# Unified_Circuit.net
KiCad netlist of a schematic drawn in EAGLE
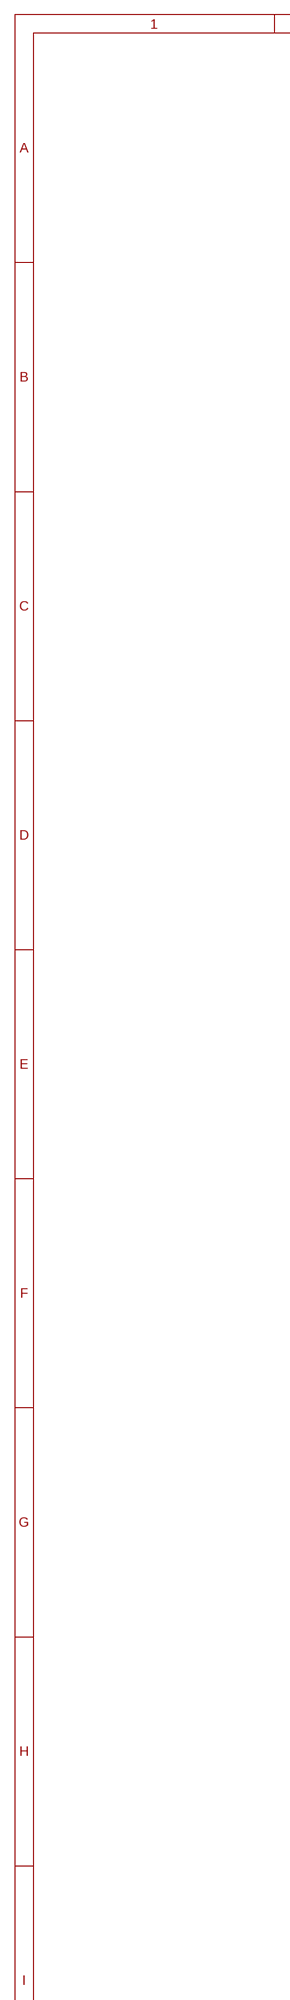
[diagram p0: schematic, sheet 1, part 1 of 2]
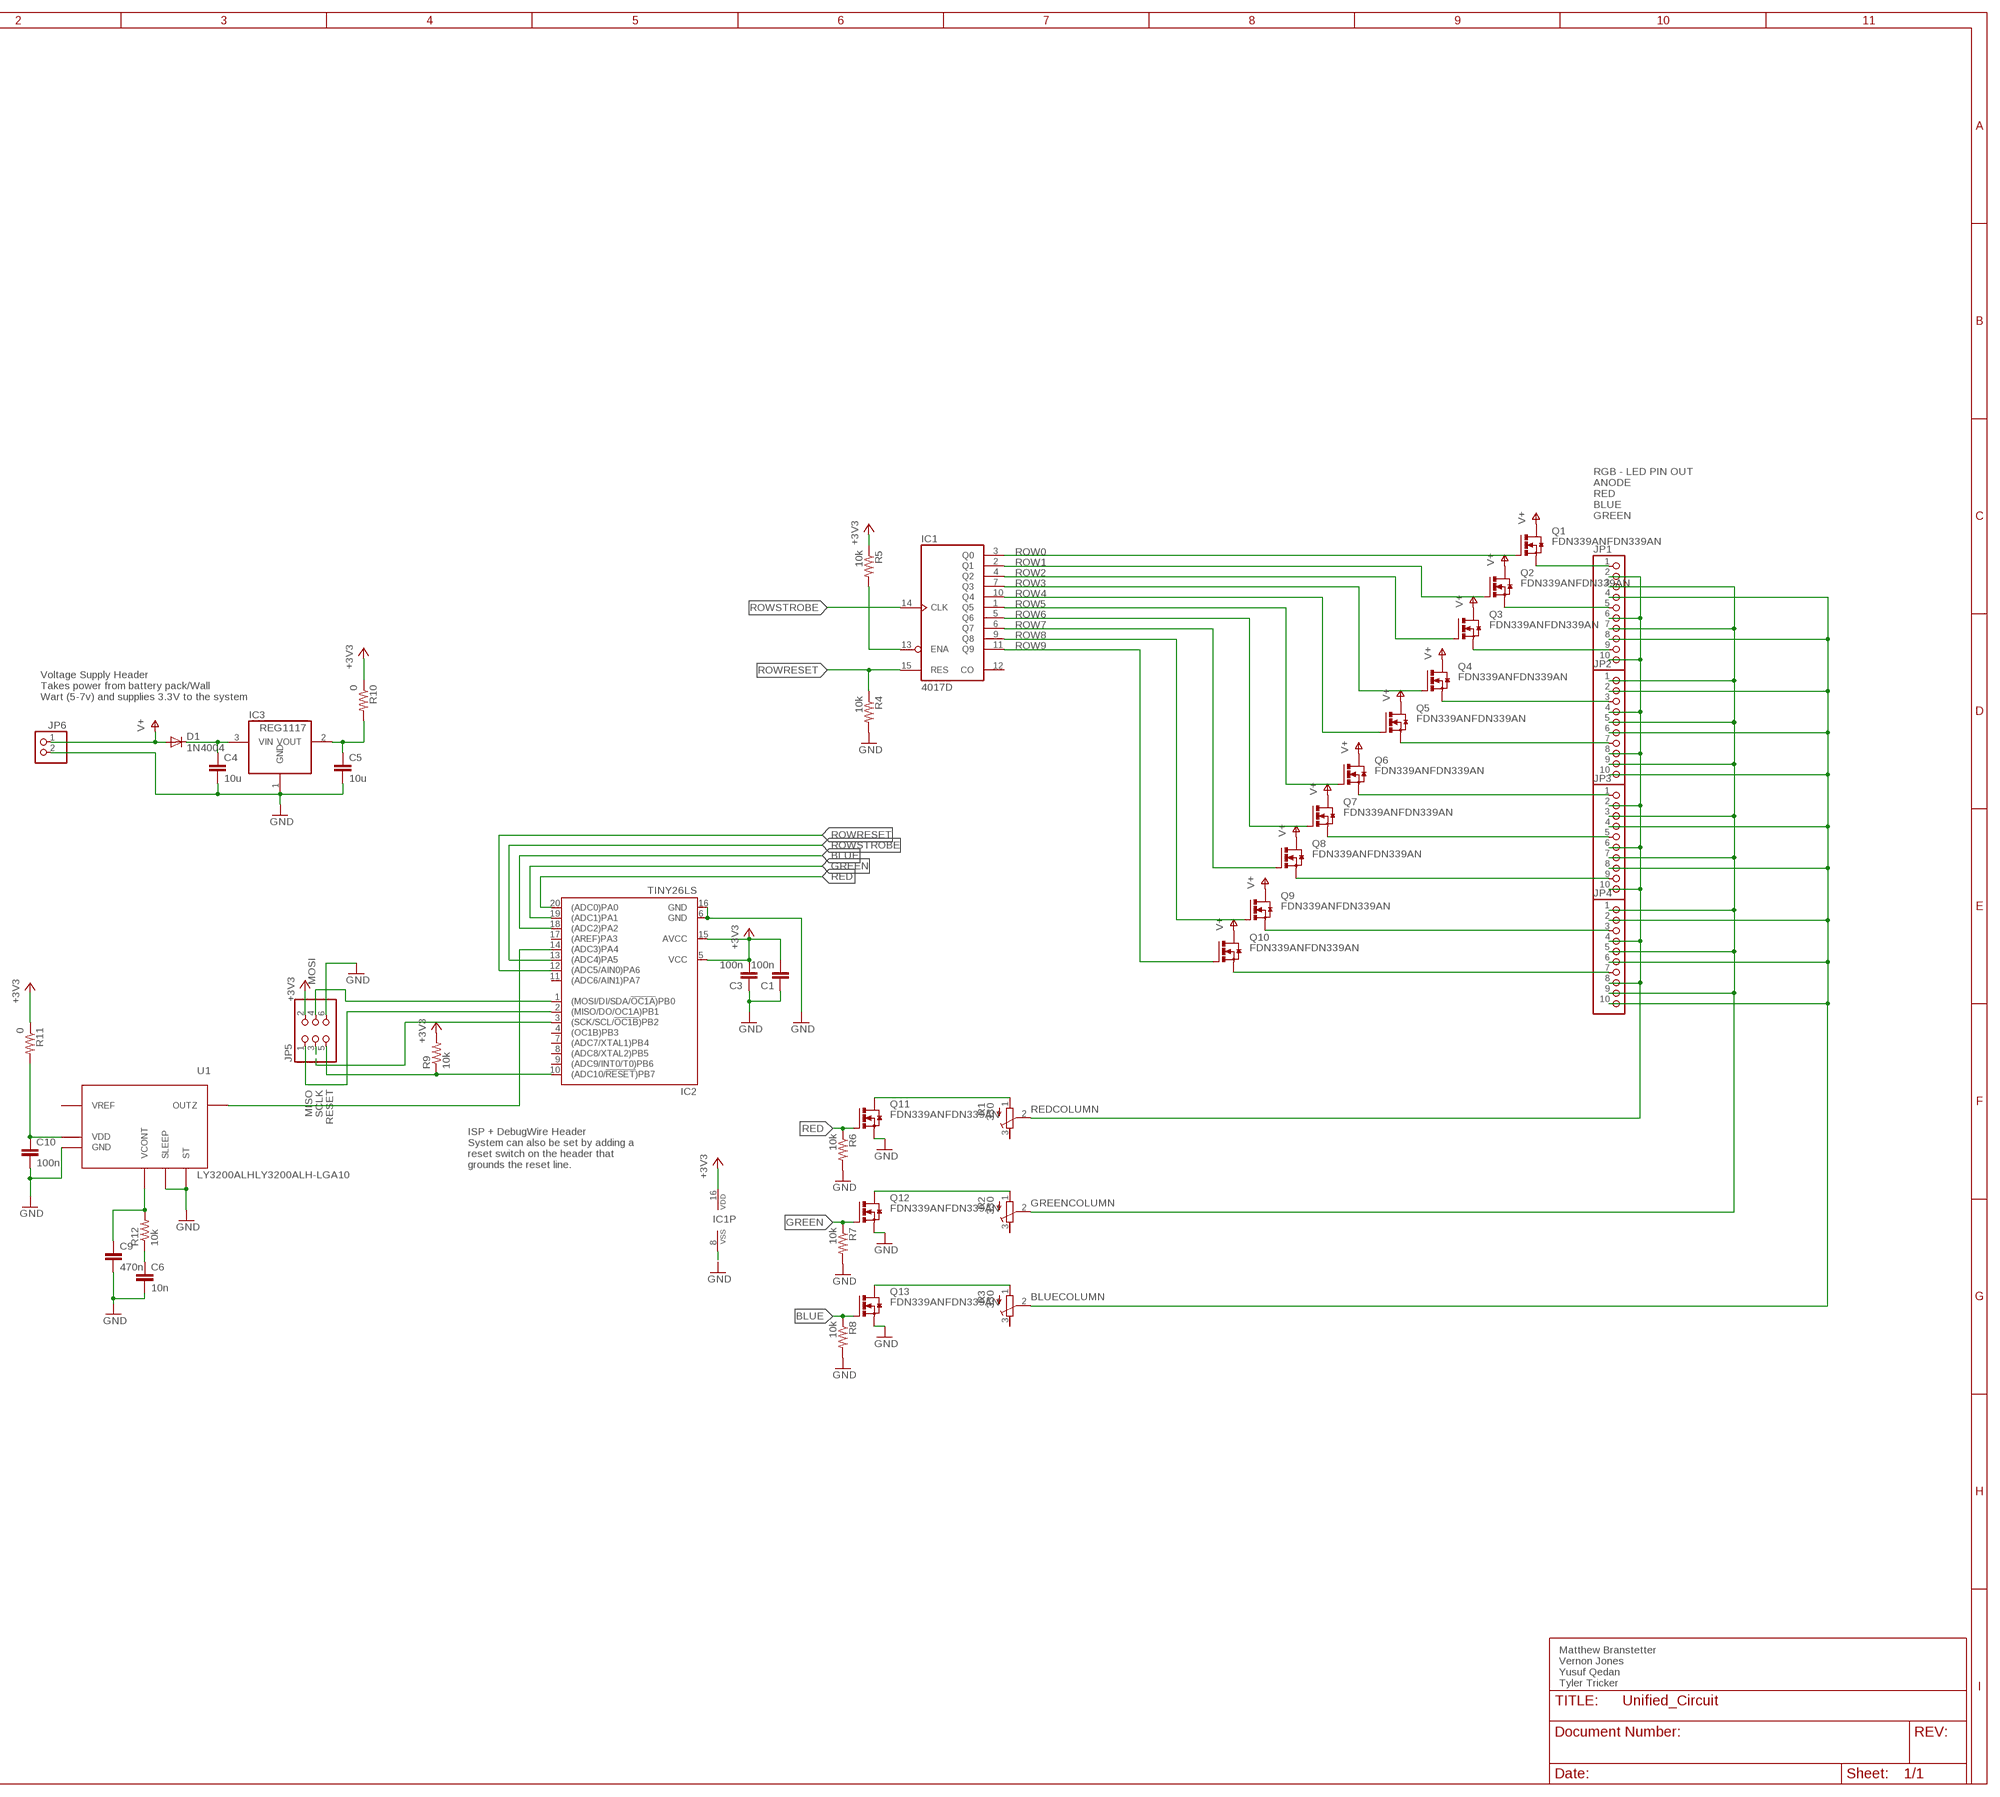
[diagram p1: schematic, sheet 1, part 2 of 2]

(export (version "E")
  (design (tool "Eeschema 10.0.6"))
  (components
    (comp (ref "C1")
      (value "100n")
      (footprint "eagle-import:C0805")
      (libsource (lib "eagle-import") (part "C-EUC0805"))
    )
    (comp (ref "C3")
      (value "100n")
      (footprint "eagle-import:C0805")
      (libsource (lib "eagle-import") (part "C-EUC0805"))
    )
    (comp (ref "C4")
      (value "10u")
      (footprint "eagle-import:C0805")
      (libsource (lib "eagle-import") (part "C-EUC0805"))
    )
    (comp (ref "C5")
      (value "10u")
      (footprint "eagle-import:C0805")
      (libsource (lib "eagle-import") (part "C-EUC0805"))
    )
    (comp (ref "C6")
      (value "10n")
      (footprint "eagle-import:C0805")
      (libsource (lib "eagle-import") (part "C-EUC0805"))
    )
    (comp (ref "C9")
      (value "470n")
      (footprint "eagle-import:C0805")
      (libsource (lib "eagle-import") (part "C-EUC0805"))
    )
    (comp (ref "C10")
      (value "100n")
      (footprint "eagle-import:C0805")
      (libsource (lib "eagle-import") (part "C-EUC0805"))
    )
    (comp (ref "D1")
      (value "1N4004")
      (footprint "eagle-import:DO41-10")
      (libsource (lib "eagle-import") (part "1N4004"))
    )
    (comp (ref "IC1")
      (value "4017D")
      (footprint "eagle-import:SO16")
      (libsource (lib "eagle-import") (part "4017D"))
    )
    (comp (ref "IC2")
      (value "TINY26LS")
      (footprint "eagle-import:SO20L")
      (fields (field (name "MPN") "ATTINY26L-8SU"))
      (libsource (lib "eagle-import") (part "TINY26SL"))
    )
    (comp (ref "IC3")
      (value "REG1117")
      (footprint "eagle-import:SOT223")
      (libsource (lib "eagle-import") (part "REG1117"))
    )
    (comp (ref "JP1")
      (value "PINHD-1X10/90")
      (footprint "eagle-import:1X10_90")
      (libsource (lib "eagle-import") (part "PINHD-1X10/90"))
    )
    (comp (ref "JP2")
      (value "PINHD-1X10/90")
      (footprint "eagle-import:1X10_90")
      (libsource (lib "eagle-import") (part "PINHD-1X10/90"))
    )
    (comp (ref "JP3")
      (value "PINHD-1X10/90")
      (footprint "eagle-import:1X10_90")
      (libsource (lib "eagle-import") (part "PINHD-1X10/90"))
    )
    (comp (ref "JP4")
      (value "PINHD-1X10/90")
      (footprint "eagle-import:1X10_90")
      (libsource (lib "eagle-import") (part "PINHD-1X10/90"))
    )
    (comp (ref "JP5")
      (value "PINHD-2X3")
      (footprint "eagle-import:2X03")
      (libsource (lib "eagle-import") (part "PINHD-2X3"))
    )
    (comp (ref "JP6")
      (value "PINHD-1X2")
      (footprint "eagle-import:1X02")
      (libsource (lib "eagle-import") (part "PINHD-1X2"))
    )
    (comp (ref "Q1")
      (value "FDN339ANFDN339AN")
      (footprint "eagle-import:SSOT-3")
      (libsource (lib "eagle-import") (part "FDN339ANFDN339AN"))
    )
    (comp (ref "Q2")
      (value "FDN339ANFDN339AN")
      (footprint "eagle-import:SSOT-3")
      (libsource (lib "eagle-import") (part "FDN339ANFDN339AN"))
    )
    (comp (ref "Q3")
      (value "FDN339ANFDN339AN")
      (footprint "eagle-import:SSOT-3")
      (libsource (lib "eagle-import") (part "FDN339ANFDN339AN"))
    )
    (comp (ref "Q4")
      (value "FDN339ANFDN339AN")
      (footprint "eagle-import:SSOT-3")
      (libsource (lib "eagle-import") (part "FDN339ANFDN339AN"))
    )
    (comp (ref "Q5")
      (value "FDN339ANFDN339AN")
      (footprint "eagle-import:SSOT-3")
      (libsource (lib "eagle-import") (part "FDN339ANFDN339AN"))
    )
    (comp (ref "Q6")
      (value "FDN339ANFDN339AN")
      (footprint "eagle-import:SSOT-3")
      (libsource (lib "eagle-import") (part "FDN339ANFDN339AN"))
    )
    (comp (ref "Q7")
      (value "FDN339ANFDN339AN")
      (footprint "eagle-import:SSOT-3")
      (libsource (lib "eagle-import") (part "FDN339ANFDN339AN"))
    )
    (comp (ref "Q8")
      (value "FDN339ANFDN339AN")
      (footprint "eagle-import:SSOT-3")
      (libsource (lib "eagle-import") (part "FDN339ANFDN339AN"))
    )
    (comp (ref "Q9")
      (value "FDN339ANFDN339AN")
      (footprint "eagle-import:SSOT-3")
      (libsource (lib "eagle-import") (part "FDN339ANFDN339AN"))
    )
    (comp (ref "Q10")
      (value "FDN339ANFDN339AN")
      (footprint "eagle-import:SSOT-3")
      (libsource (lib "eagle-import") (part "FDN339ANFDN339AN"))
    )
    (comp (ref "Q11")
      (value "FDN339ANFDN339AN")
      (footprint "eagle-import:SSOT-3")
      (libsource (lib "eagle-import") (part "FDN339ANFDN339AN"))
    )
    (comp (ref "Q12")
      (value "FDN339ANFDN339AN")
      (footprint "eagle-import:SSOT-3")
      (libsource (lib "eagle-import") (part "FDN339ANFDN339AN"))
    )
    (comp (ref "Q13")
      (value "FDN339ANFDN339AN")
      (footprint "eagle-import:SSOT-3")
      (libsource (lib "eagle-import") (part "FDN339ANFDN339AN"))
    )
    (comp (ref "R1")
      (value "330")
      (footprint "eagle-import:RTRIM3224W")
      (libsource (lib "eagle-import") (part "R-TRIMM3224W"))
    )
    (comp (ref "R2")
      (value "330")
      (footprint "eagle-import:RTRIM3224W")
      (libsource (lib "eagle-import") (part "R-TRIMM3224W"))
    )
    (comp (ref "R3")
      (value "330")
      (footprint "eagle-import:RTRIM3224W")
      (libsource (lib "eagle-import") (part "R-TRIMM3224W"))
    )
    (comp (ref "R4")
      (value "10k")
      (footprint "eagle-import:R0805")
      (libsource (lib "eagle-import") (part "R-US_R0805"))
    )
    (comp (ref "R5")
      (value "10k")
      (footprint "eagle-import:R0805")
      (libsource (lib "eagle-import") (part "R-US_R0805"))
    )
    (comp (ref "R6")
      (value "10k")
      (footprint "eagle-import:R0805")
      (libsource (lib "eagle-import") (part "R-US_R0805"))
    )
    (comp (ref "R7")
      (value "10k")
      (footprint "eagle-import:R0805")
      (libsource (lib "eagle-import") (part "R-US_R0805"))
    )
    (comp (ref "R8")
      (value "10k")
      (footprint "eagle-import:R0805")
      (libsource (lib "eagle-import") (part "R-US_R0805"))
    )
    (comp (ref "R9")
      (value "10k")
      (footprint "eagle-import:R0805")
      (libsource (lib "eagle-import") (part "R-US_R0805"))
    )
    (comp (ref "R10")
      (value "0")
      (footprint "eagle-import:R0805")
      (libsource (lib "eagle-import") (part "R-US_R0805"))
    )
    (comp (ref "R11")
      (value "0")
      (footprint "eagle-import:R0805")
      (libsource (lib "eagle-import") (part "R-US_R0805"))
    )
    (comp (ref "R12")
      (value "10k")
      (footprint "eagle-import:R0805")
      (libsource (lib "eagle-import") (part "R-US_R0805"))
    )
    (comp (ref "U1")
      (value "LY3200ALHLY3200ALH-LGA10")
      (footprint "eagle-import:LGA10")
      (libsource (lib "eagle-import") (part "LY3200ALHLY3200ALH-LGA10"))
    )
  )
  (nets
    (net (code "1") (name "+3V3") (class "Default")
      (node (ref "C1") (pin "2") (pinfunction "2_2") (pintype "passive"))
      (node (ref "C3") (pin "2") (pinfunction "2_2") (pintype "passive"))
      (node (ref "IC1") (pin "16") (pinfunction "VDD_16") (pintype "power_in"))
      (node (ref "IC2") (pin "15") (pinfunction "AVCC_15") (pintype "power_in"))
      (node (ref "IC2") (pin "5") (pinfunction "VCC_5") (pintype "power_in"))
      (node (ref "JP5") (pin "2") (pinfunction "2_2") (pintype "passive"))
      (node (ref "R10") (pin "1") (pinfunction "1_1") (pintype "passive"))
      (node (ref "R11") (pin "1") (pinfunction "1_1") (pintype "passive"))
      (node (ref "R5") (pin "1") (pinfunction "1_1") (pintype "passive"))
      (node (ref "R9") (pin "2") (pinfunction "2_2") (pintype "passive"))
    )
    (net (code "2") (name "/BLUECOLUMN") (class "Default")
      (node (ref "JP1") (pin "4") (pinfunction "4_4") (pintype "passive"))
      (node (ref "JP1") (pin "8") (pinfunction "8_8") (pintype "passive"))
      (node (ref "JP2") (pin "10") (pinfunction "10_10") (pintype "passive"))
      (node (ref "JP2") (pin "2") (pinfunction "2_2") (pintype "passive"))
      (node (ref "JP2") (pin "6") (pinfunction "6_6") (pintype "passive"))
      (node (ref "JP3") (pin "4") (pinfunction "4_4") (pintype "passive"))
      (node (ref "JP3") (pin "8") (pinfunction "8_8") (pintype "passive"))
      (node (ref "JP4") (pin "10") (pinfunction "10_10") (pintype "passive"))
      (node (ref "JP4") (pin "2") (pinfunction "2_2") (pintype "passive"))
      (node (ref "JP4") (pin "6") (pinfunction "6_6") (pintype "passive"))
      (node (ref "R3") (pin "2") (pinfunction "S_2") (pintype "passive"))
    )
    (net (code "3") (name "/GREENCOLUMN") (class "Default")
      (node (ref "JP1") (pin "3") (pinfunction "3_3") (pintype "passive"))
      (node (ref "JP1") (pin "7") (pinfunction "7_7") (pintype "passive"))
      (node (ref "JP2") (pin "1") (pinfunction "1_1") (pintype "passive"))
      (node (ref "JP2") (pin "5") (pinfunction "5_5") (pintype "passive"))
      (node (ref "JP2") (pin "9") (pinfunction "9_9") (pintype "passive"))
      (node (ref "JP3") (pin "3") (pinfunction "3_3") (pintype "passive"))
      (node (ref "JP3") (pin "7") (pinfunction "7_7") (pintype "passive"))
      (node (ref "JP4") (pin "1") (pinfunction "1_1") (pintype "passive"))
      (node (ref "JP4") (pin "5") (pinfunction "5_5") (pintype "passive"))
      (node (ref "JP4") (pin "9") (pinfunction "9_9") (pintype "passive"))
      (node (ref "R2") (pin "2") (pinfunction "S_2") (pintype "passive"))
    )
    (net (code "4") (name "/MISO") (class "Default")
      (node (ref "IC2") (pin "2") (pinfunction "(MISO/DO/OC1A)PB1_2") (pintype "bidirectional"))
      (node (ref "JP5") (pin "1") (pinfunction "1_1") (pintype "passive"))
    )
    (net (code "5") (name "/MOSI") (class "Default")
      (node (ref "IC2") (pin "1") (pinfunction "(MOSI/DI/SDA/~{OC1A})PB0_1") (pintype "bidirectional"))
      (node (ref "JP5") (pin "4") (pinfunction "4_4") (pintype "passive"))
    )
    (net (code "6") (name "/REDCOLUMN") (class "Default")
      (node (ref "JP1") (pin "10") (pinfunction "10_10") (pintype "passive"))
      (node (ref "JP1") (pin "2") (pinfunction "2_2") (pintype "passive"))
      (node (ref "JP1") (pin "6") (pinfunction "6_6") (pintype "passive"))
      (node (ref "JP2") (pin "4") (pinfunction "4_4") (pintype "passive"))
      (node (ref "JP2") (pin "8") (pinfunction "8_8") (pintype "passive"))
      (node (ref "JP3") (pin "10") (pinfunction "10_10") (pintype "passive"))
      (node (ref "JP3") (pin "2") (pinfunction "2_2") (pintype "passive"))
      (node (ref "JP3") (pin "6") (pinfunction "6_6") (pintype "passive"))
      (node (ref "JP4") (pin "4") (pinfunction "4_4") (pintype "passive"))
      (node (ref "JP4") (pin "8") (pinfunction "8_8") (pintype "passive"))
      (node (ref "R1") (pin "2") (pinfunction "S_2") (pintype "passive"))
    )
    (net (code "7") (name "/RESET") (class "Default")
      (node (ref "IC2") (pin "10") (pinfunction "(ADC10/~{RESET})PB7_10") (pintype "bidirectional"))
      (node (ref "JP5") (pin "5") (pinfunction "5_5") (pintype "passive"))
      (node (ref "R9") (pin "1") (pinfunction "1_1") (pintype "passive"))
    )
    (net (code "8") (name "/ROW0") (class "Default")
      (node (ref "IC1") (pin "3") (pinfunction "Q0_3") (pintype "output"))
      (node (ref "Q1") (pin "P$2") (pinfunction "G_P$2") (pintype "passive"))
    )
    (net (code "9") (name "/ROW1") (class "Default")
      (node (ref "IC1") (pin "2") (pinfunction "Q1_2") (pintype "output"))
      (node (ref "Q2") (pin "P$2") (pinfunction "G_P$2") (pintype "passive"))
    )
    (net (code "10") (name "/ROW2") (class "Default")
      (node (ref "IC1") (pin "4") (pinfunction "Q2_4") (pintype "output"))
      (node (ref "Q3") (pin "P$2") (pinfunction "G_P$2") (pintype "passive"))
    )
    (net (code "11") (name "/ROW3") (class "Default")
      (node (ref "IC1") (pin "7") (pinfunction "Q3_7") (pintype "output"))
      (node (ref "Q4") (pin "P$2") (pinfunction "G_P$2") (pintype "passive"))
    )
    (net (code "12") (name "/ROW4") (class "Default")
      (node (ref "IC1") (pin "10") (pinfunction "Q4_10") (pintype "output"))
      (node (ref "Q5") (pin "P$2") (pinfunction "G_P$2") (pintype "passive"))
    )
    (net (code "13") (name "/ROW5") (class "Default")
      (node (ref "IC1") (pin "1") (pinfunction "Q5_1") (pintype "output"))
      (node (ref "Q6") (pin "P$2") (pinfunction "G_P$2") (pintype "passive"))
    )
    (net (code "14") (name "/ROW6") (class "Default")
      (node (ref "IC1") (pin "5") (pinfunction "Q6_5") (pintype "output"))
      (node (ref "Q7") (pin "P$2") (pinfunction "G_P$2") (pintype "passive"))
    )
    (net (code "15") (name "/ROW7") (class "Default")
      (node (ref "IC1") (pin "6") (pinfunction "Q7_6") (pintype "output"))
      (node (ref "Q8") (pin "P$2") (pinfunction "G_P$2") (pintype "passive"))
    )
    (net (code "16") (name "/ROW8") (class "Default")
      (node (ref "IC1") (pin "9") (pinfunction "Q8_9") (pintype "output"))
      (node (ref "Q9") (pin "P$2") (pinfunction "G_P$2") (pintype "passive"))
    )
    (net (code "17") (name "/ROW9") (class "Default")
      (node (ref "IC1") (pin "11") (pinfunction "Q9_11") (pintype "output"))
      (node (ref "Q10") (pin "P$2") (pinfunction "G_P$2") (pintype "passive"))
    )
    (net (code "18") (name "/SCLK") (class "Default")
      (node (ref "IC2") (pin "3") (pinfunction "(SCK/SCL/~{OC1B})PB2_3") (pintype "bidirectional"))
      (node (ref "JP5") (pin "3") (pinfunction "3_3") (pintype "passive"))
    )
    (net (code "19") (name "BLUE") (class "Default")
      (node (ref "IC2") (pin "18") (pinfunction "(ADC2)PA2_18") (pintype "bidirectional"))
      (node (ref "Q13") (pin "P$2") (pinfunction "G_P$2") (pintype "passive"))
      (node (ref "R8") (pin "1") (pinfunction "1_1") (pintype "passive"))
    )
    (net (code "20") (name "GND") (class "Default")
      (node (ref "C1") (pin "1") (pinfunction "1_1") (pintype "passive"))
      (node (ref "C10") (pin "2") (pinfunction "2_2") (pintype "passive"))
      (node (ref "C3") (pin "1") (pinfunction "1_1") (pintype "passive"))
      (node (ref "C4") (pin "2") (pinfunction "2_2") (pintype "passive"))
      (node (ref "C5") (pin "2") (pinfunction "2_2") (pintype "passive"))
      (node (ref "C6") (pin "2") (pinfunction "2_2") (pintype "passive"))
      (node (ref "C9") (pin "2") (pinfunction "2_2") (pintype "passive"))
      (node (ref "IC1") (pin "8") (pinfunction "VSS_8") (pintype "power_in"))
      (node (ref "IC2") (pin "16") (pinfunction "GND_16") (pintype "power_in"))
      (node (ref "IC2") (pin "6") (pinfunction "GND_6") (pintype "power_in"))
      (node (ref "IC3") (pin "1") (pinfunction "GND_1") (pintype "power_in"))
      (node (ref "JP5") (pin "6") (pinfunction "6_6") (pintype "passive"))
      (node (ref "JP6") (pin "2") (pinfunction "2_2") (pintype "passive"))
      (node (ref "Q11") (pin "P$3") (pinfunction "S_P$3") (pintype "passive"))
      (node (ref "Q12") (pin "P$3") (pinfunction "S_P$3") (pintype "passive"))
      (node (ref "Q13") (pin "P$3") (pinfunction "S_P$3") (pintype "passive"))
      (node (ref "R4") (pin "2") (pinfunction "2_2") (pintype "passive"))
      (node (ref "R6") (pin "2") (pinfunction "2_2") (pintype "passive"))
      (node (ref "R7") (pin "2") (pinfunction "2_2") (pintype "passive"))
      (node (ref "R8") (pin "2") (pinfunction "2_2") (pintype "passive"))
      (node (ref "U1") (pin "P$2") (pinfunction "ST_P$2") (pintype "input"))
      (node (ref "U1") (pin "P$4") (pinfunction "GND_P$4") (pintype "power_in"))
      (node (ref "U1") (pin "P$8") (pinfunction "SLEEP_P$8") (pintype "input"))
    )
    (net (code "21") (name "GREEN") (class "Default")
      (node (ref "IC2") (pin "19") (pinfunction "(ADC1)PA1_19") (pintype "bidirectional"))
      (node (ref "Q12") (pin "P$2") (pinfunction "G_P$2") (pintype "passive"))
      (node (ref "R7") (pin "1") (pinfunction "1_1") (pintype "passive"))
    )
    (net (code "22") (name "Net-(C6-Pad1)") (class "Default")
      (node (ref "C6") (pin "1") (pinfunction "1_1") (pintype "passive"))
      (node (ref "R12") (pin "1") (pinfunction "1_1") (pintype "passive"))
    )
    (net (code "23") (name "Net-(C10-Pad1)") (class "Default")
      (node (ref "C10") (pin "1") (pinfunction "1_1") (pintype "passive"))
      (node (ref "R11") (pin "2") (pinfunction "2_2") (pintype "passive"))
      (node (ref "U1") (pin "P$1") (pinfunction "VDD_P$1") (pintype "power_in"))
      (node (ref "U1") (pin "P$9") (pinfunction "VDD_P$9") (pintype "power_in"))
    )
    (net (code "24") (name "Net-(IC1A-ENA)") (class "Default")
      (node (ref "IC1") (pin "13") (pinfunction "ENA_13") (pintype "input"))
      (node (ref "R5") (pin "2") (pinfunction "2_2") (pintype "passive"))
    )
    (net (code "25") (name "Net-(IC2-(ADC3)PA4)") (class "Default")
      (node (ref "IC2") (pin "14") (pinfunction "(ADC3)PA4_14") (pintype "bidirectional"))
      (node (ref "U1") (pin "P$6") (pinfunction "OUTZ_P$6") (pintype "output"))
    )
    (net (code "26") (name "Net-(IC3-VIN)") (class "Default")
      (node (ref "C4") (pin "1") (pinfunction "1_1") (pintype "passive"))
      (node (ref "D1") (pin "C") (pinfunction "C_C") (pintype "passive"))
      (node (ref "IC3") (pin "3") (pinfunction "VIN_3") (pintype "input"))
    )
    (net (code "27") (name "Net-(IC3-VOUT)") (class "Default")
      (node (ref "C5") (pin "1") (pinfunction "1_1") (pintype "passive"))
      (node (ref "IC3") (pin "2") (pinfunction "VOUT_2") (pintype "output"))
      (node (ref "R10") (pin "2") (pinfunction "2_2") (pintype "passive"))
    )
    (net (code "28") (name "Net-(Q1-S)") (class "Default")
      (node (ref "JP1") (pin "1") (pinfunction "1_1") (pintype "passive"))
      (node (ref "Q1") (pin "P$3") (pinfunction "S_P$3") (pintype "passive"))
    )
    (net (code "29") (name "Net-(Q2-S)") (class "Default")
      (node (ref "JP1") (pin "5") (pinfunction "5_5") (pintype "passive"))
      (node (ref "Q2") (pin "P$3") (pinfunction "S_P$3") (pintype "passive"))
    )
    (net (code "30") (name "Net-(Q3-S)") (class "Default")
      (node (ref "JP1") (pin "9") (pinfunction "9_9") (pintype "passive"))
      (node (ref "Q3") (pin "P$3") (pinfunction "S_P$3") (pintype "passive"))
    )
    (net (code "31") (name "Net-(Q4-S)") (class "Default")
      (node (ref "JP2") (pin "3") (pinfunction "3_3") (pintype "passive"))
      (node (ref "Q4") (pin "P$3") (pinfunction "S_P$3") (pintype "passive"))
    )
    (net (code "32") (name "Net-(Q5-S)") (class "Default")
      (node (ref "JP2") (pin "7") (pinfunction "7_7") (pintype "passive"))
      (node (ref "Q5") (pin "P$3") (pinfunction "S_P$3") (pintype "passive"))
    )
    (net (code "33") (name "Net-(Q6-S)") (class "Default")
      (node (ref "JP3") (pin "1") (pinfunction "1_1") (pintype "passive"))
      (node (ref "Q6") (pin "P$3") (pinfunction "S_P$3") (pintype "passive"))
    )
    (net (code "34") (name "Net-(Q7-S)") (class "Default")
      (node (ref "JP3") (pin "5") (pinfunction "5_5") (pintype "passive"))
      (node (ref "Q7") (pin "P$3") (pinfunction "S_P$3") (pintype "passive"))
    )
    (net (code "35") (name "Net-(Q8-S)") (class "Default")
      (node (ref "JP3") (pin "9") (pinfunction "9_9") (pintype "passive"))
      (node (ref "Q8") (pin "P$3") (pinfunction "S_P$3") (pintype "passive"))
    )
    (net (code "36") (name "Net-(Q9-S)") (class "Default")
      (node (ref "JP4") (pin "3") (pinfunction "3_3") (pintype "passive"))
      (node (ref "Q9") (pin "P$3") (pinfunction "S_P$3") (pintype "passive"))
    )
    (net (code "37") (name "Net-(Q10-S)") (class "Default")
      (node (ref "JP4") (pin "7") (pinfunction "7_7") (pintype "passive"))
      (node (ref "Q10") (pin "P$3") (pinfunction "S_P$3") (pintype "passive"))
    )
    (net (code "38") (name "Net-(Q11-D)") (class "Default")
      (node (ref "Q11") (pin "P$1") (pinfunction "D_P$1") (pintype "passive"))
      (node (ref "R1") (pin "1") (pinfunction "A_1") (pintype "passive"))
    )
    (net (code "39") (name "Net-(Q12-D)") (class "Default")
      (node (ref "Q12") (pin "P$1") (pinfunction "D_P$1") (pintype "passive"))
      (node (ref "R2") (pin "1") (pinfunction "A_1") (pintype "passive"))
    )
    (net (code "40") (name "Net-(Q13-D)") (class "Default")
      (node (ref "Q13") (pin "P$1") (pinfunction "D_P$1") (pintype "passive"))
      (node (ref "R3") (pin "1") (pinfunction "A_1") (pintype "passive"))
    )
    (net (code "41") (name "Net-(U1-VCONT)") (class "Default")
      (node (ref "C9") (pin "1") (pinfunction "1_1") (pintype "passive"))
      (node (ref "R12") (pin "2") (pinfunction "2_2") (pintype "passive"))
      (node (ref "U1") (pin "P$3") (pinfunction "VCONT_P$3") (pintype "input"))
    )
    (net (code "42") (name "RED") (class "Default")
      (node (ref "IC2") (pin "20") (pinfunction "(ADC0)PA0_20") (pintype "bidirectional"))
      (node (ref "Q11") (pin "P$2") (pinfunction "G_P$2") (pintype "passive"))
      (node (ref "R6") (pin "1") (pinfunction "1_1") (pintype "passive"))
    )
    (net (code "43") (name "ROWRESET") (class "Default")
      (node (ref "IC1") (pin "15") (pinfunction "RES_15") (pintype "input"))
      (node (ref "IC2") (pin "12") (pinfunction "(ADC5/AIN0)PA6_12") (pintype "bidirectional"))
      (node (ref "R4") (pin "1") (pinfunction "1_1") (pintype "passive"))
    )
    (net (code "44") (name "ROWSTROBE") (class "Default")
      (node (ref "IC1") (pin "14") (pinfunction "CLK_14") (pintype "input"))
      (node (ref "IC2") (pin "13") (pinfunction "(ADC4)PA5_13") (pintype "bidirectional"))
    )
    (net (code "45") (name "V+") (class "Default")
      (node (ref "D1") (pin "A") (pinfunction "A_A") (pintype "passive"))
      (node (ref "JP6") (pin "1") (pinfunction "1_1") (pintype "passive"))
      (node (ref "Q1") (pin "P$1") (pinfunction "D_P$1") (pintype "passive"))
      (node (ref "Q10") (pin "P$1") (pinfunction "D_P$1") (pintype "passive"))
      (node (ref "Q2") (pin "P$1") (pinfunction "D_P$1") (pintype "passive"))
      (node (ref "Q3") (pin "P$1") (pinfunction "D_P$1") (pintype "passive"))
      (node (ref "Q4") (pin "P$1") (pinfunction "D_P$1") (pintype "passive"))
      (node (ref "Q5") (pin "P$1") (pinfunction "D_P$1") (pintype "passive"))
      (node (ref "Q6") (pin "P$1") (pinfunction "D_P$1") (pintype "passive"))
      (node (ref "Q7") (pin "P$1") (pinfunction "D_P$1") (pintype "passive"))
      (node (ref "Q8") (pin "P$1") (pinfunction "D_P$1") (pintype "passive"))
      (node (ref "Q9") (pin "P$1") (pinfunction "D_P$1") (pintype "passive"))
    )
    (net (code "46") (name "unconnected-(IC1A-CO-Pad12)") (class "Default")
      (node (ref "IC1") (pin "12") (pinfunction "CO_12") (pintype "output"))
    )
    (net (code "47") (name "unconnected-(IC2-(ADC6{slash}AIN1)PA7-Pad11)") (class "Default")
      (node (ref "IC2") (pin "11") (pinfunction "(ADC6/AIN1)PA7_11") (pintype "bidirectional"))
    )
    (net (code "48") (name "unconnected-(IC2-(ADC7{slash}XTAL1)PB4-Pad7)") (class "Default")
      (node (ref "IC2") (pin "7") (pinfunction "(ADC7/XTAL1)PB4_7") (pintype "bidirectional"))
    )
    (net (code "49") (name "unconnected-(IC2-(ADC8{slash}XTAL2)PB5-Pad8)") (class "Default")
      (node (ref "IC2") (pin "8") (pinfunction "(ADC8/XTAL2)PB5_8") (pintype "bidirectional"))
    )
    (net (code "50") (name "unconnected-(IC2-(ADC9{slash}INT0{slash}T0)PB6-Pad9)") (class "Default")
      (node (ref "IC2") (pin "9") (pinfunction "(ADC9/INT0/T0)PB6_9") (pintype "bidirectional"))
    )
    (net (code "51") (name "unconnected-(IC2-(AREF)PA3-Pad17)") (class "Default")
      (node (ref "IC2") (pin "17") (pinfunction "(AREF)PA3_17") (pintype "bidirectional"))
    )
    (net (code "52") (name "unconnected-(IC2-(OC1B)PB3-Pad4)") (class "Default")
      (node (ref "IC2") (pin "4") (pinfunction "(OC1B)PB3_4") (pintype "bidirectional"))
    )
    (net (code "53") (name "unconnected-(R1-E-Pad3)") (class "Default")
      (node (ref "R1") (pin "3") (pinfunction "E_3") (pintype "passive"))
    )
    (net (code "54") (name "unconnected-(R2-E-Pad3)") (class "Default")
      (node (ref "R2") (pin "3") (pinfunction "E_3") (pintype "passive"))
    )
    (net (code "55") (name "unconnected-(R3-E-Pad3)") (class "Default")
      (node (ref "R3") (pin "3") (pinfunction "E_3") (pintype "passive"))
    )
    (net (code "56") (name "unconnected-(U1-VREF-PadP$7)") (class "Default")
      (node (ref "U1") (pin "P$7") (pinfunction "VREF_P$7") (pintype "output"))
    )
  )
)
